# GPS_-_NEO-M8T.net
KiCad netlist of a schematic drawn in Altium Designer
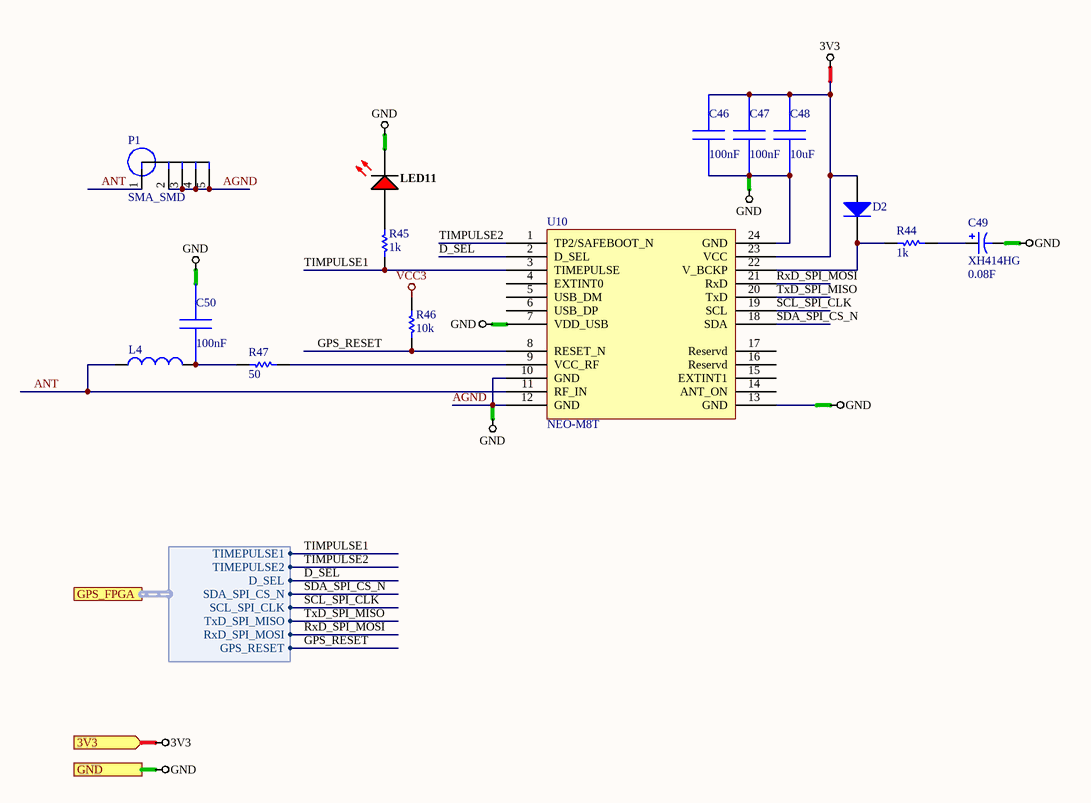
[diagram p0: GPS - NEO-M8T.SchDoc]

(export (version "E")
  (design (tool "Eeschema 10.0.6"))
  (components
    (comp (ref "C46")
      (value "100nF")
      (footprint "C-0603")
      (description "C0603C104K3RACTU")
      (libsource (lib "TI WEBENCH") (part "Cinx"))
    )
    (comp (ref "C47")
      (value "100nF")
      (footprint "C-0603")
      (description "C0603C104K3RACTU")
      (libsource (lib "TI WEBENCH") (part "Cinx"))
    )
    (comp (ref "C48")
      (value "10uF")
      (footprint "1206")
      (description "GRM31CR61E106KA1")
      (fields (field (name "MANUFACTURER PART NUMBER") "GRM31CR61E106KA12L"))
      (libsource (lib "TI WEBENCH") (part "Cin"))
    )
    (comp (ref "C49")
      (value "XH414HG")
      (footprint "RB7.6-15")
      (description "Polarized Capacitor (Radial)")
      (fields (field (name "ALTIUM_VALUE") "0.08F") (field (name "PUBLISHER") "Altium Limited"))
      (libsource (lib "Miscellaneous Devices") (part "Cap Pol1"))
    )
    (comp (ref "C50")
      (value "100nF")
      (footprint "C-0603")
      (description "C0603C104K3RACTU")
      (libsource (lib "TI WEBENCH") (part "Cinx"))
    )
    (comp (ref "D2")
      (value "~")
      (footprint "SMC")
      (description "Default Diode")
      (fields (field (name "PUBLISHER") "Altium Limited"))
      (libsource (lib "Miscellaneous Devices") (part "Diode"))
    )
    (comp (ref "L4")
      (value "~")
      (footprint "0402-A")
      (description "Inductor")
      (fields (field (name "PUBLISHER") "Altium Limited"))
      (libsource (lib "Miscellaneous Devices") (part "Inductor"))
    )
    (comp (ref "LED11")
      (value "0402-LED-RED")
      (footprint "LED_0402")
      (description "0402 LED,RED")
      (fields (field (name "MANUFACTURER PART NUMBER") "LTST-C190KRKT"))
      (libsource (lib "FPGA-pcie") (part "LED_RED_A1K2-2"))
    )
    (comp (ref "P1") (value "SMA_SMD") (footprint "SMA") (libsource (lib "PCB_Project1") (part "SMA_SMD")))
    (comp (ref "R44")
      (value "1k")
      (footprint "RESC0402(1005)40_L")
      (description "Semiconductor Resistor")
      (fields
        (field (name "MANUFACTURER") "Generic Components")
        (field (name "PUBLISHER") "Altium Hobart Technology Centre")
      )
      (libsource (lib "Miscellaneous Devices") (part "Res Semi"))
    )
    (comp (ref "R45")
      (value "1k")
      (footprint "RESC0402(1005)40_L")
      (description "Semiconductor Resistor")
      (fields
        (field (name "MANUFACTURER") "Generic Components")
        (field (name "PUBLISHER") "Altium Hobart Technology Centre")
      )
      (libsource (lib "") (part "Res Semi_1"))
    )
    (comp (ref "R46")
      (value "10k")
      (footprint "RESC0402(1005)40_L")
      (description "Semiconductor Resistor")
      (fields
        (field (name "MANUFACTURER") "Generic Components")
        (field (name "PUBLISHER") "Altium Hobart Technology Centre")
      )
      (libsource (lib "") (part "Res Semi_1"))
    )
    (comp (ref "R47")
      (value "50")
      (footprint "RESC0402(1005)40_L")
      (description "Semiconductor Resistor")
      (fields
        (field (name "MANUFACTURER") "Generic Components")
        (field (name "PUBLISHER") "Altium Hobart Technology Centre")
      )
      (libsource (lib "Miscellaneous Devices") (part "Res Semi"))
    )
    (comp (ref "U10") (value "NEO-M8T") (footprint "NEO") (libsource (lib "neom8t") (part "NEO-M8T")))
  )
  (nets
    (net (code "2") (name "/ANT") (class "Default")
      (node (ref "L4") (pin "1") (pinfunction "1_1") (pintype "passive"))
      (node (ref "P1") (pin "1") (pinfunction "1_1") (pintype "passive"))
      (node (ref "U10") (pin "11") (pinfunction "RF_IN_11") (pintype "passive"))
    )
    (net (code "3") (name "/D_SEL") (class "Default")
      (node (ref "U10") (pin "2") (pinfunction "D_SEL_2") (pintype "passive"))
    )
    (net (code "4") (name "/GPS_RESET") (class "Default")
      (node (ref "R46") (pin "2") (pinfunction "2_2") (pintype "passive"))
      (node (ref "U10") (pin "8") (pinfunction "RESET_N_8") (pintype "passive"))
    )
    (net (code "5") (name "/RxD_SPI_MOSI") (class "Default")
      (node (ref "U10") (pin "21") (pinfunction "RxD_21") (pintype "passive"))
    )
    (net (code "6") (name "/SCL_SPI_CLK") (class "Default")
      (node (ref "U10") (pin "19") (pinfunction "SCL_19") (pintype "passive"))
    )
    (net (code "7") (name "/SDA_SPI_CS_N") (class "Default")
      (node (ref "U10") (pin "18") (pinfunction "SDA_18") (pintype "passive"))
    )
    (net (code "8") (name "/TIMPULSE1") (class "Default")
      (node (ref "R45") (pin "1") (pinfunction "1_1") (pintype "passive"))
      (node (ref "U10") (pin "3") (pinfunction "TIMEPULSE_3") (pintype "passive"))
    )
    (net (code "9") (name "/TIMPULSE2") (class "Default")
      (node (ref "U10") (pin "1") (pinfunction "TP2/SAFEBOOT_N_1") (pintype "passive"))
    )
    (net (code "10") (name "/TxD_SPI_MISO") (class "Default")
      (node (ref "U10") (pin "20") (pinfunction "TxD_20") (pintype "passive"))
    )
    (net (code "12") (name "3V3") (class "Default")
      (node (ref "C46") (pin "1") (pinfunction "1_1") (pintype "passive"))
      (node (ref "C47") (pin "1") (pinfunction "1_1") (pintype "passive"))
      (node (ref "C48") (pin "1") (pinfunction "1_1") (pintype "passive"))
      (node (ref "D2") (pin "1") (pinfunction "A_1") (pintype "passive"))
      (node (ref "U10") (pin "23") (pinfunction "VCC_23") (pintype "passive"))
    )
    (net (code "13") (name "GND") (class "Default")
      (node (ref "C46") (pin "2") (pinfunction "2_2") (pintype "passive"))
      (node (ref "C47") (pin "2") (pinfunction "2_2") (pintype "passive"))
      (node (ref "C48") (pin "2") (pinfunction "2_2") (pintype "passive"))
      (node (ref "C49") (pin "2") (pinfunction "2_2") (pintype "passive"))
      (node (ref "C50") (pin "1") (pinfunction "1_1") (pintype "passive"))
      (node (ref "LED11") (pin "2") (pinfunction "K_2") (pintype "passive"))
      (node (ref "P1") (pin "2") (pinfunction "2_2") (pintype "passive"))
      (node (ref "P1") (pin "3") (pinfunction "3_3") (pintype "passive"))
      (node (ref "P1") (pin "4") (pinfunction "4_4") (pintype "passive"))
      (node (ref "P1") (pin "5") (pinfunction "5_5") (pintype "passive"))
      (node (ref "U10") (pin "10") (pinfunction "GND_10") (pintype "passive"))
      (node (ref "U10") (pin "12") (pinfunction "GND_12") (pintype "passive"))
      (node (ref "U10") (pin "13") (pinfunction "GND_13") (pintype "passive"))
      (node (ref "U10") (pin "24") (pinfunction "GND_24") (pintype "passive"))
      (node (ref "U10") (pin "7") (pinfunction "VDD_USB_7") (pintype "passive"))
    )
    (net (code "14") (name "Net-(C49-Pad1)") (class "Default")
      (node (ref "C49") (pin "1") (pinfunction "1_1") (pintype "passive"))
      (node (ref "R44") (pin "2") (pinfunction "2_2") (pintype "passive"))
    )
    (net (code "15") (name "Net-(C50-Pad2)") (class "Default")
      (node (ref "C50") (pin "2") (pinfunction "2_2") (pintype "passive"))
      (node (ref "L4") (pin "2") (pinfunction "2_2") (pintype "passive"))
      (node (ref "R47") (pin "1") (pinfunction "1_1") (pintype "passive"))
    )
    (net (code "16") (name "Net-(D2-K)") (class "Default")
      (node (ref "D2") (pin "2") (pinfunction "K_2") (pintype "passive"))
      (node (ref "R44") (pin "1") (pinfunction "1_1") (pintype "passive"))
      (node (ref "U10") (pin "22") (pinfunction "V_BCKP_22") (pintype "passive"))
    )
    (net (code "17") (name "Net-(LED11-A)") (class "Default")
      (node (ref "LED11") (pin "1") (pinfunction "A_1") (pintype "passive"))
      (node (ref "R45") (pin "2") (pinfunction "2_2") (pintype "passive"))
    )
    (net (code "18") (name "Net-(U10-VCC_RF)") (class "Default")
      (node (ref "R47") (pin "2") (pinfunction "2_2") (pintype "passive"))
      (node (ref "U10") (pin "9") (pinfunction "VCC_RF_9") (pintype "passive"))
    )
    (net (code "19") (name "VCC3") (class "Default")
      (node (ref "R46") (pin "1") (pinfunction "1_1") (pintype "passive"))
    )
    (net (code "20") (name "unconnected-(U10-ANT_ON-Pad14)") (class "Default")
      (node (ref "U10") (pin "14") (pinfunction "ANT_ON_14") (pintype "passive"))
    )
    (net (code "21") (name "unconnected-(U10-EXTINT0-Pad4)") (class "Default")
      (node (ref "U10") (pin "4") (pinfunction "EXTINT0_4") (pintype "passive"))
    )
    (net (code "22") (name "unconnected-(U10-EXTINT1-Pad15)") (class "Default")
      (node (ref "U10") (pin "15") (pinfunction "EXTINT1_15") (pintype "passive"))
    )
    (net (code "23") (name "unconnected-(U10-Reservd-Pad16)") (class "Default")
      (node (ref "U10") (pin "16") (pinfunction "Reservd_16") (pintype "passive"))
    )
    (net (code "24") (name "unconnected-(U10-Reservd-Pad17)") (class "Default")
      (node (ref "U10") (pin "17") (pinfunction "Reservd_17") (pintype "passive"))
    )
    (net (code "25") (name "unconnected-(U10-USB_DM-Pad5)") (class "Default")
      (node (ref "U10") (pin "5") (pinfunction "USB_DM_5") (pintype "passive"))
    )
    (net (code "26") (name "unconnected-(U10-USB_DP-Pad6)") (class "Default")
      (node (ref "U10") (pin "6") (pinfunction "USB_DP_6") (pintype "passive"))
    )
  )
)
